# sensors_power.net
KiCad netlist of a schematic drawn in Altium Designer
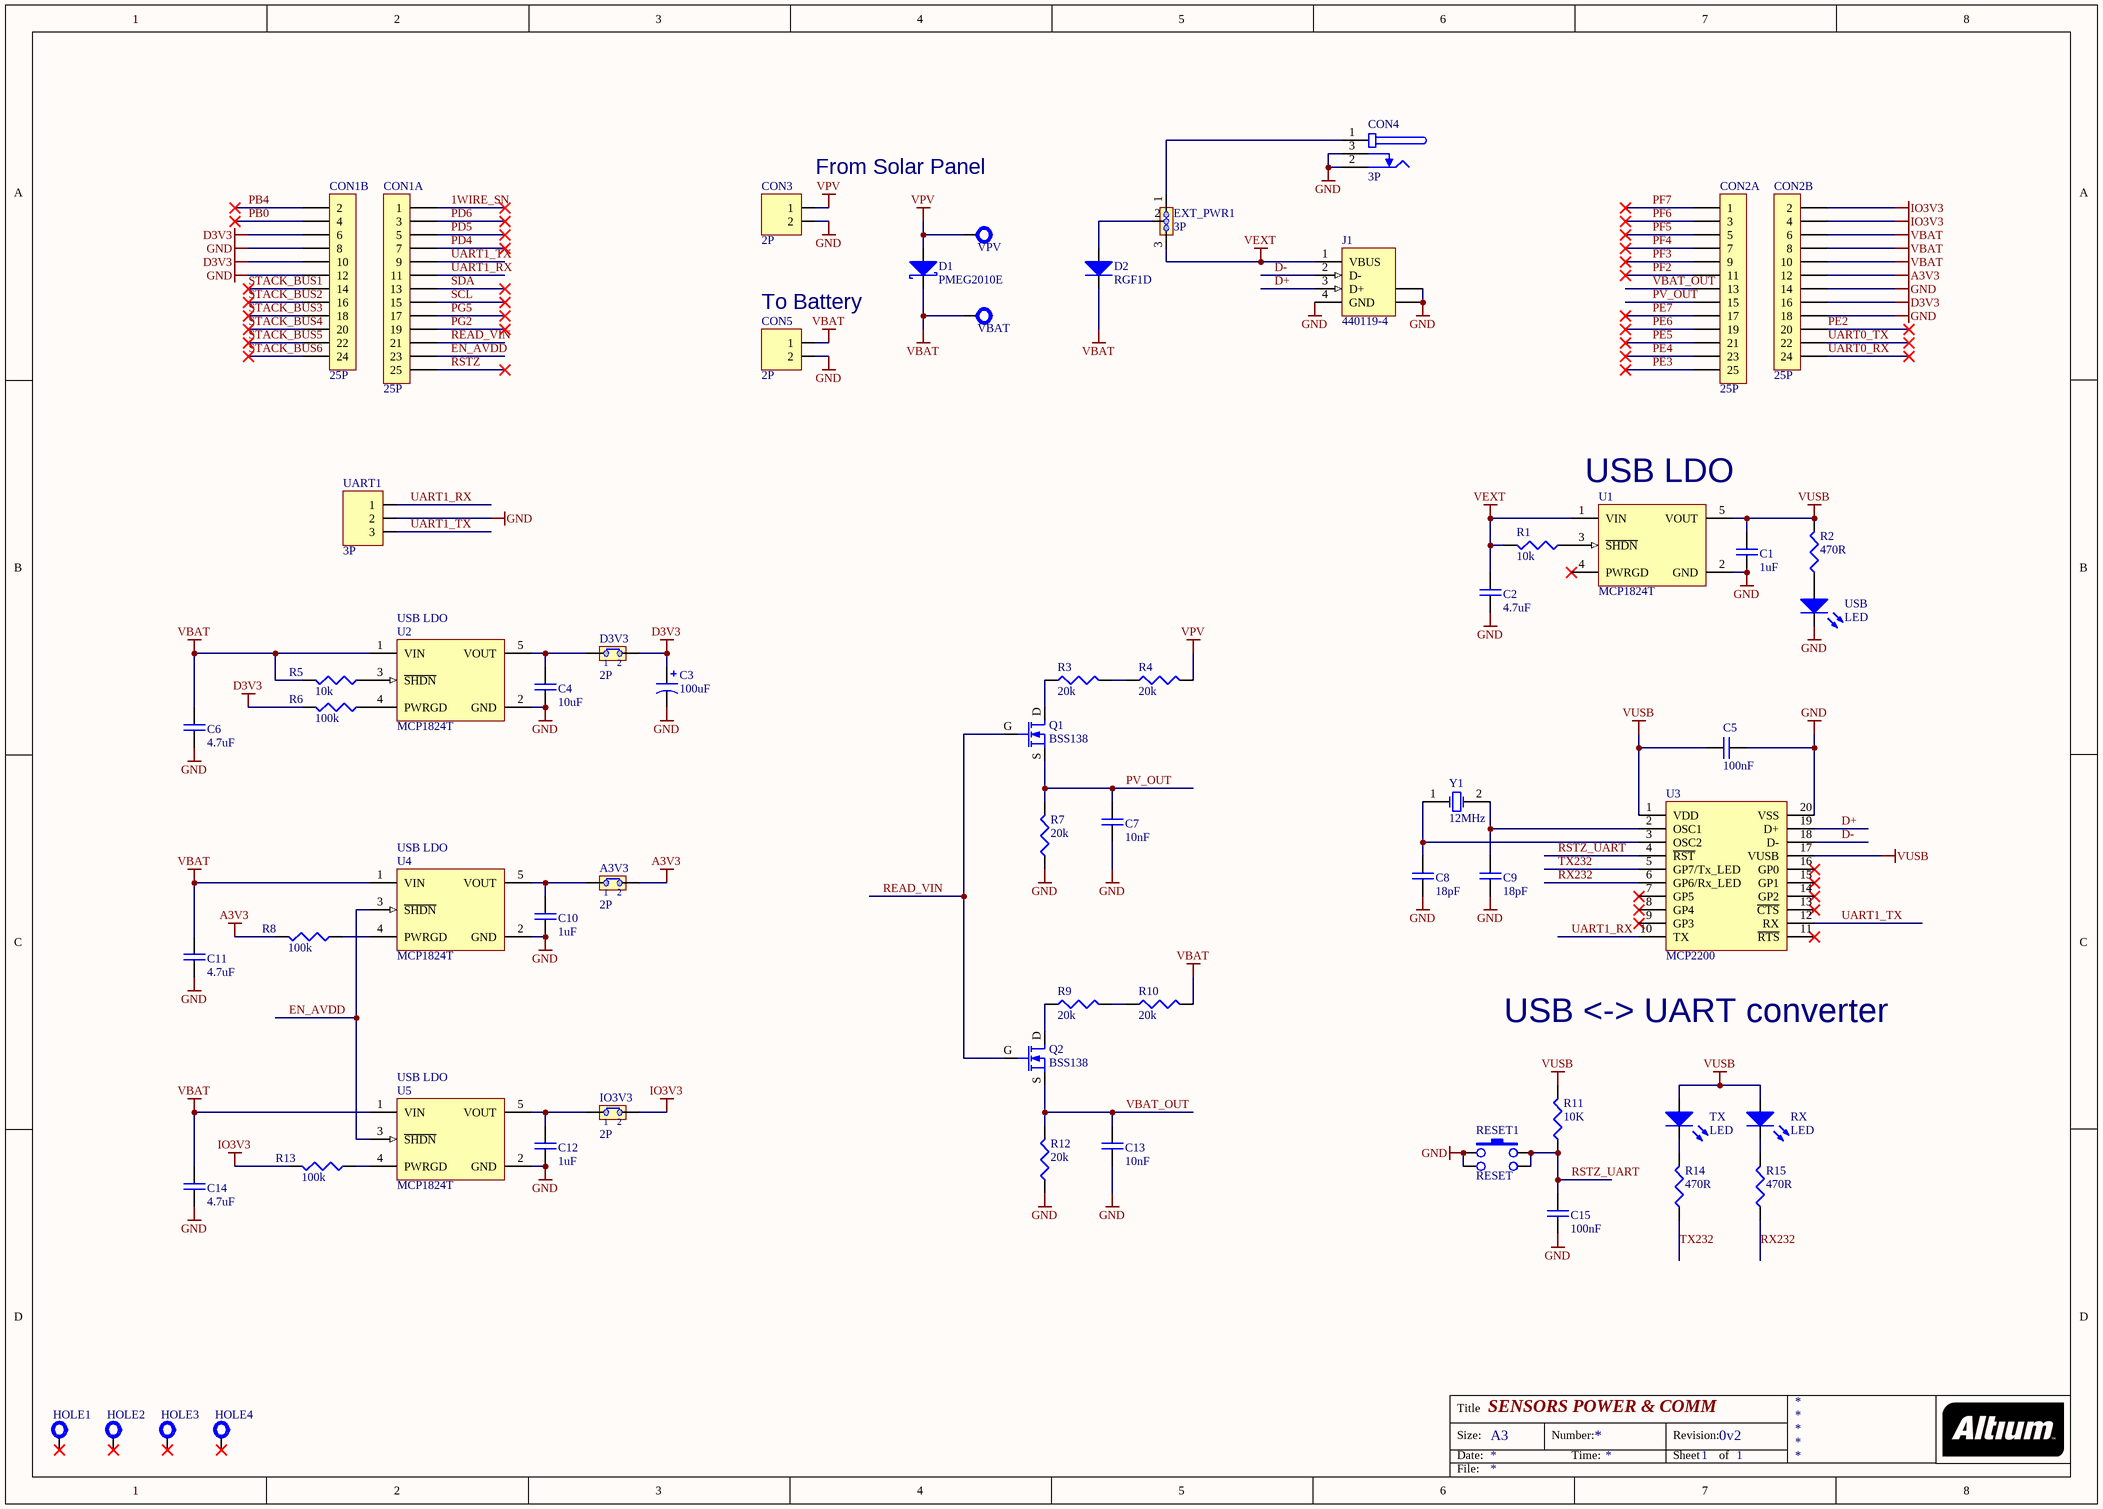
[diagram p0: sensors_power.SchDoc]

(export (version "E")
  (design (tool "Eeschema 10.0.6"))
  (components
    (comp (ref "A3V3")
      (value "2P")
      (footprint "SIP-2")
      (description "2-pin Jumper")
      (fields (field (name "OWNER") "Nuno Brum"))
      (libsource (lib "Alcetronics_EM") (part "JMP2"))
    )
    (comp (ref "C1")
      (value "1uF")
      (footprint "0805")
      (description "Capacitor")
      (fields (field (name "OWNER") "Nuno Brum"))
      (libsource (lib "Alcetronics_Devices") (part "CAP"))
    )
    (comp (ref "C2")
      (value "4.7uF")
      (footprint "0805")
      (description "Capacitor")
      (fields (field (name "OWNER") "Nuno Brum"))
      (libsource (lib "Alcetronics_Devices") (part "CAP"))
    )
    (comp (ref "C3")
      (value "100uF")
      (footprint "RADIAL-2.5MM")
      (description "Polarized Capacitor")
      (fields (field (name "OWNER") "Nuno Brum"))
      (libsource (lib "Alcetronics_Devices") (part "CAP POL"))
    )
    (comp (ref "C4")
      (value "10uF")
      (footprint "0805")
      (description "Capacitor")
      (fields (field (name "OWNER") "Nuno Brum"))
      (libsource (lib "Alcetronics_Devices") (part "CAP"))
    )
    (comp (ref "C5")
      (value "100nF")
      (footprint "0603")
      (description "Capacitor")
      (fields (field (name "OWNER") "Nuno Brum"))
      (libsource (lib "Alcetronics_Devices") (part "CAP"))
    )
    (comp (ref "C6")
      (value "4.7uF")
      (footprint "0805")
      (description "Capacitor")
      (fields (field (name "OWNER") "Nuno Brum"))
      (libsource (lib "Alcetronics_Devices") (part "CAP"))
    )
    (comp (ref "C7")
      (value "10nF")
      (footprint "0603")
      (description "Capacitor")
      (fields (field (name "OWNER") "Nuno Brum"))
      (libsource (lib "Alcetronics_Devices") (part "CAP"))
    )
    (comp (ref "C8")
      (value "18pF")
      (footprint "0603")
      (description "Capacitor")
      (fields (field (name "OWNER") "Nuno Brum"))
      (libsource (lib "Alcetronics_Devices") (part "CAP"))
    )
    (comp (ref "C9")
      (value "18pF")
      (footprint "0603")
      (description "Capacitor")
      (fields (field (name "OWNER") "Nuno Brum"))
      (libsource (lib "Alcetronics_Devices") (part "CAP"))
    )
    (comp (ref "C10")
      (value "1uF")
      (footprint "0805")
      (description "Capacitor")
      (fields (field (name "OWNER") "Nuno Brum"))
      (libsource (lib "Alcetronics_Devices") (part "CAP"))
    )
    (comp (ref "C11")
      (value "4.7uF")
      (footprint "0805")
      (description "Capacitor")
      (fields (field (name "OWNER") "Nuno Brum"))
      (libsource (lib "Alcetronics_Devices") (part "CAP"))
    )
    (comp (ref "C12")
      (value "1uF")
      (footprint "0805")
      (description "Capacitor")
      (fields (field (name "OWNER") "Nuno Brum"))
      (libsource (lib "Alcetronics_Devices") (part "CAP"))
    )
    (comp (ref "C13")
      (value "10nF")
      (footprint "0603")
      (description "Capacitor")
      (fields (field (name "OWNER") "Nuno Brum"))
      (libsource (lib "Alcetronics_Devices") (part "CAP"))
    )
    (comp (ref "C14")
      (value "4.7uF")
      (footprint "0805")
      (description "Capacitor")
      (fields (field (name "OWNER") "Nuno Brum"))
      (libsource (lib "Alcetronics_Devices") (part "CAP"))
    )
    (comp (ref "C15")
      (value "100nF")
      (footprint "0603")
      (description "Capacitor")
      (fields (field (name "OWNER") "Nuno Brum"))
      (libsource (lib "Alcetronics_Devices") (part "CAP"))
    )
    (comp (ref "CON1")
      (value "25P")
      (footprint "DF9-25")
      (description "Connector 25 Pins")
      (fields (field (name "OWNER") "Ricardo Rodrigues"))
      (libsource (lib "") (part "CON25_1"))
    )
    (comp (ref "CON2")
      (value "25P")
      (footprint "DF9-25")
      (description "Connector 25 Pins")
      (fields (field (name "OWNER") "Ricardo Rodrigues"))
      (libsource (lib "Alcetronics_EM") (part "CON25"))
    )
    (comp (ref "CON3")
      (value "2P")
      (footprint "JST-2MM")
      (description "Connector 2 pins")
      (fields (field (name "OWNER") "Rui Rebelo"))
      (libsource (lib "Alcetronics_EM") (part "CON02"))
    )
    (comp (ref "CON4")
      (value "3P")
      (footprint "JACKPOW/PD-2.5MM-TH")
      (description "Jack Power with insertion detect")
      (fields (field (name "OWNER") "Gonçalo Costa"))
      (libsource (lib "Alcetronics_EM") (part "JACK POWER PD"))
    )
    (comp (ref "CON5")
      (value "2P")
      (footprint "INTERLOCK2-5MM")
      (description "Connector 2 pins")
      (fields (field (name "OWNER") "Rui Rebelo"))
      (libsource (lib "Alcetronics_EM") (part "CON02"))
    )
    (comp (ref "D1")
      (value "PMEG2010E")
      (footprint "SOD-123")
      (description "Small Signal Schottky Diode")
      (fields (field (name "OWNER") "Nuno Brum"))
      (libsource (lib "Alcetronics_Devices") (part "Diode Schottky"))
    )
    (comp (ref "D2")
      (value "RGF1D")
      (footprint "DO-214BA")
      (description "Vishay Standard Avalanche Sinterglass Diode")
      (fields (field (name "OWNER") "Nuno Brum"))
      (libsource (lib "Alcetronics_Devices") (part "Diode"))
    )
    (comp (ref "D3V3")
      (value "2P")
      (footprint "SIP-2")
      (description "2-pin Jumper")
      (fields (field (name "OWNER") "Nuno Brum"))
      (libsource (lib "Alcetronics_EM") (part "JMP2"))
    )
    (comp (ref "EXT_PWR1")
      (value "3P")
      (footprint "SIP-3")
      (description "3-Jumper")
      (fields (field (name "OWNER") "Nuno Brum"))
      (libsource (lib "Alcetronics_EM") (part "JMP3"))
    )
    (comp (ref "HOLE1")
      (value "HOLE")
      (footprint "NPTH-3MM")
      (description "PCB Fixation Hole M3")
      (fields (field (name "OWNER") "Nuno Brum"))
      (libsource (lib "Alcetronics_EM") (part "PCB HOLE"))
    )
    (comp (ref "HOLE2")
      (value "HOLE")
      (footprint "NPTH-3MM")
      (description "PCB Fixation Hole M3")
      (fields (field (name "OWNER") "Nuno Brum"))
      (libsource (lib "Alcetronics_EM") (part "PCB HOLE"))
    )
    (comp (ref "HOLE3")
      (value "HOLE")
      (footprint "NPTH-3MM")
      (description "PCB Fixation Hole M3")
      (fields (field (name "OWNER") "Nuno Brum"))
      (libsource (lib "Alcetronics_EM") (part "PCB HOLE"))
    )
    (comp (ref "HOLE4")
      (value "HOLE")
      (footprint "NPTH-3MM")
      (description "PCB Fixation Hole M3")
      (fields (field (name "OWNER") "Nuno Brum"))
      (libsource (lib "Alcetronics_EM") (part "PCB HOLE"))
    )
    (comp (ref "IO3V3")
      (value "2P")
      (footprint "SIP-2")
      (description "2-pin Jumper")
      (fields (field (name "OWNER") "Nuno Brum"))
      (libsource (lib "Alcetronics_EM") (part "JMP2"))
    )
    (comp (ref "J1")
      (value "440119-4")
      (footprint "440119")
      (description "USB 1.1, Right Angle, Thru-Hole, B Type, Receptacle, 4 Position, Black")
      (fields (field (name "PUBLISHER") "Altium Limited"))
      (libsource (lib "Alcetronics_EM") (part "440119-4"))
    )
    (comp (ref "Q1")
      (value "BSS138")
      (footprint "SOT-23@GSD")
      (description "N-Channel Logic Level Enhancement Mode Field Effect Transistor")
      (fields (field (name "OWNER") "Nuno Brum"))
      (libsource (lib "Alcetronics_Devices") (part "MOSFET-N"))
    )
    (comp (ref "Q2")
      (value "BSS138")
      (footprint "SOT-23@GSD")
      (description "N-Channel Logic Level Enhancement Mode Field Effect Transistor")
      (fields (field (name "OWNER") "Nuno Brum"))
      (libsource (lib "Alcetronics_Devices") (part "MOSFET-N"))
    )
    (comp (ref "R1")
      (value "10k")
      (footprint "0603")
      (description "Resistor")
      (fields (field (name "OWNER") "Nuno Brum"))
      (libsource (lib "Alcetronics_Devices") (part "RES"))
    )
    (comp (ref "R2")
      (value "470R")
      (footprint "0603")
      (description "Resistor")
      (fields (field (name "OWNER") "Nuno Brum"))
      (libsource (lib "Alcetronics_Devices") (part "RES"))
    )
    (comp (ref "R3")
      (value "20k")
      (footprint "0603")
      (description "Resistor")
      (fields (field (name "OWNER") "Nuno Brum"))
      (libsource (lib "Alcetronics_Devices") (part "RES"))
    )
    (comp (ref "R4")
      (value "20k")
      (footprint "0603")
      (description "Resistor")
      (fields (field (name "OWNER") "Nuno Brum"))
      (libsource (lib "Alcetronics_Devices") (part "RES"))
    )
    (comp (ref "R5")
      (value "10k")
      (footprint "0603")
      (description "Resistor")
      (fields (field (name "OWNER") "Nuno Brum"))
      (libsource (lib "Alcetronics_Devices") (part "RES"))
    )
    (comp (ref "R6")
      (value "100k")
      (footprint "0603")
      (description "Resistor")
      (fields (field (name "OWNER") "Nuno Brum"))
      (libsource (lib "Alcetronics_Devices") (part "RES"))
    )
    (comp (ref "R7")
      (value "20k")
      (footprint "0603")
      (description "Resistor")
      (fields (field (name "OWNER") "Nuno Brum"))
      (libsource (lib "Alcetronics_Devices") (part "RES"))
    )
    (comp (ref "R8")
      (value "100k")
      (footprint "0603")
      (description "Resistor")
      (fields (field (name "OWNER") "Nuno Brum"))
      (libsource (lib "Alcetronics_Devices") (part "RES"))
    )
    (comp (ref "R9")
      (value "20k")
      (footprint "0603")
      (description "Resistor")
      (fields (field (name "OWNER") "Nuno Brum"))
      (libsource (lib "Alcetronics_Devices") (part "RES"))
    )
    (comp (ref "R10")
      (value "20k")
      (footprint "0603")
      (description "Resistor")
      (fields (field (name "OWNER") "Nuno Brum"))
      (libsource (lib "Alcetronics_Devices") (part "RES"))
    )
    (comp (ref "R11")
      (value "10K")
      (footprint "0603")
      (description "Resistor")
      (fields (field (name "OWNER") "Nuno Brum"))
      (libsource (lib "Alcetronics_Devices") (part "RES"))
    )
    (comp (ref "R12")
      (value "20k")
      (footprint "0603")
      (description "Resistor")
      (fields (field (name "OWNER") "Nuno Brum"))
      (libsource (lib "Alcetronics_Devices") (part "RES"))
    )
    (comp (ref "R13")
      (value "100k")
      (footprint "0603")
      (description "Resistor")
      (fields (field (name "OWNER") "Nuno Brum"))
      (libsource (lib "Alcetronics_Devices") (part "RES"))
    )
    (comp (ref "R14")
      (value "470R")
      (footprint "0603")
      (description "Resistor")
      (fields (field (name "OWNER") "Nuno Brum"))
      (libsource (lib "Alcetronics_Devices") (part "RES"))
    )
    (comp (ref "R15")
      (value "470R")
      (footprint "0603")
      (description "Resistor")
      (fields (field (name "OWNER") "Nuno Brum"))
      (libsource (lib "Alcetronics_Devices") (part "RES"))
    )
    (comp (ref "RESET1")
      (value "RESET")
      (footprint "MICROSWITCH")
      (description "Switch Push Button")
      (fields (field (name "OWNER") "Nuno Brum"))
      (libsource (lib "Alcetronics_EM") (part "SW1"))
    )
    (comp (ref "RX")
      (value "LED")
      (footprint "0805@DIODE")
      (description "Light emitting diode")
      (fields (field (name "OWNER") "Nuno Brum"))
      (libsource (lib "Alcetronics_Devices") (part "LED"))
    )
    (comp (ref "TX")
      (value "LED")
      (footprint "0805@DIODE")
      (description "Light emitting diode")
      (fields (field (name "OWNER") "Nuno Brum"))
      (libsource (lib "Alcetronics_Devices") (part "LED"))
    )
    (comp (ref "U1")
      (value "MCP1824T")
      (footprint "SOT-23-5")
      (fields (field (name "PUBLISHER") "Altium Limited"))
      (libsource (lib "Alcetronics_IC") (part "MCP1824T"))
    )
    (comp (ref "U2")
      (value "MCP1824T")
      (footprint "SOT-23-5")
      (fields (field (name "PUBLISHER") "Altium Limited"))
      (libsource (lib "Alcetronics_IC") (part "MCP1824T"))
    )
    (comp (ref "U3")
      (value "MCP2200")
      (footprint "SOIC-20")
      (description "USB to Serial interface")
      (fields (field (name "PUBLISHER") "Altium Limited"))
      (libsource (lib "Alcetronics_IC") (part "MCP2200"))
    )
    (comp (ref "U4")
      (value "MCP1824T")
      (footprint "SOT-23-5")
      (fields (field (name "PUBLISHER") "Altium Limited"))
      (libsource (lib "Alcetronics_IC") (part "MCP1824T"))
    )
    (comp (ref "U5")
      (value "MCP1824T")
      (footprint "SOT-23-5")
      (fields (field (name "PUBLISHER") "Altium Limited"))
      (libsource (lib "Alcetronics_IC") (part "MCP1824T"))
    )
    (comp (ref "UART1")
      (value "3P")
      (footprint "SIP-3")
      (description "Connector 3 pins")
      (fields (field (name "OWNER") "Rui Rebelo"))
      (libsource (lib "Alcetronics_EM") (part "CON03"))
    )
    (comp (ref "USB")
      (value "LED")
      (footprint "0805@DIODE")
      (description "Light emitting diode")
      (fields (field (name "OWNER") "Nuno Brum"))
      (libsource (lib "Alcetronics_Devices") (part "LED"))
    )
    (comp (ref "VBAT")
      (value "Test Point")
      (footprint "TERMINAL")
      (description "Test/Probe Point")
      (fields (field (name "OWNER") "Nuno Brum"))
      (libsource (lib "Alcetronics_EM") (part "TEST-PROBE"))
    )
    (comp (ref "VPV")
      (value "Test Point")
      (footprint "TERMINAL")
      (description "Test/Probe Point")
      (fields (field (name "OWNER") "Nuno Brum"))
      (libsource (lib "Alcetronics_EM") (part "TEST-PROBE"))
    )
    (comp (ref "Y1")
      (value "12MHz")
      (footprint "CSM-7")
      (description "Crystal Oscillator")
      (fields (field (name "PUBLISHER") "Altium Limited"))
      (libsource (lib "Alcetronics_Devices") (part "Crystal Oscillator"))
    )
  )
  (nets
    (net (code "1") (name "/1WIRE_SN") (class "Default")
      (node (ref "CON1") (pin "1") (pinfunction "1_1") (pintype "passive+no_connect"))
    )
    (net (code "2") (name "/D+") (class "Default")
      (node (ref "J1") (pin "3") (pinfunction "D+_3") (pintype "input"))
      (node (ref "U3") (pin "19") (pinfunction "D+_19") (pintype "passive"))
    )
    (net (code "3") (name "/D-") (class "Default")
      (node (ref "J1") (pin "2") (pinfunction "D-_2") (pintype "input"))
      (node (ref "U3") (pin "18") (pinfunction "D-_18") (pintype "passive"))
    )
    (net (code "4") (name "/EN_AVDD") (class "Default")
      (node (ref "CON1") (pin "23") (pinfunction "23_23") (pintype "passive"))
      (node (ref "U4") (pin "3") (pinfunction "~{SHDN}_3") (pintype "input"))
      (node (ref "U5") (pin "3") (pinfunction "~{SHDN}_3") (pintype "input"))
    )
    (net (code "5") (name "/PB0") (class "Default")
      (node (ref "CON1") (pin "4") (pinfunction "4_4") (pintype "passive+no_connect"))
    )
    (net (code "6") (name "/PB4") (class "Default")
      (node (ref "CON1") (pin "2") (pinfunction "2_2") (pintype "passive+no_connect"))
    )
    (net (code "7") (name "/PD4") (class "Default")
      (node (ref "CON1") (pin "7") (pinfunction "7_7") (pintype "passive+no_connect"))
    )
    (net (code "8") (name "/PD5") (class "Default")
      (node (ref "CON1") (pin "5") (pinfunction "5_5") (pintype "passive+no_connect"))
    )
    (net (code "9") (name "/PD6") (class "Default")
      (node (ref "CON1") (pin "3") (pinfunction "3_3") (pintype "passive+no_connect"))
    )
    (net (code "10") (name "/PE2") (class "Default")
      (node (ref "CON2") (pin "20") (pinfunction "20_20") (pintype "passive+no_connect"))
    )
    (net (code "11") (name "/PE3") (class "Default")
      (node (ref "CON2") (pin "25") (pinfunction "25_25") (pintype "passive+no_connect"))
    )
    (net (code "12") (name "/PE4") (class "Default")
      (node (ref "CON2") (pin "23") (pinfunction "23_23") (pintype "passive+no_connect"))
    )
    (net (code "13") (name "/PE5") (class "Default")
      (node (ref "CON2") (pin "21") (pinfunction "21_21") (pintype "passive+no_connect"))
    )
    (net (code "14") (name "/PE6") (class "Default")
      (node (ref "CON2") (pin "19") (pinfunction "19_19") (pintype "passive+no_connect"))
    )
    (net (code "15") (name "/PE7") (class "Default")
      (node (ref "CON2") (pin "17") (pinfunction "17_17") (pintype "passive+no_connect"))
    )
    (net (code "16") (name "/PF2") (class "Default")
      (node (ref "CON2") (pin "11") (pinfunction "11_11") (pintype "passive+no_connect"))
    )
    (net (code "17") (name "/PF3") (class "Default")
      (node (ref "CON2") (pin "9") (pinfunction "9_9") (pintype "passive+no_connect"))
    )
    (net (code "18") (name "/PF4") (class "Default")
      (node (ref "CON2") (pin "7") (pinfunction "7_7") (pintype "passive+no_connect"))
    )
    (net (code "19") (name "/PF5") (class "Default")
      (node (ref "CON2") (pin "5") (pinfunction "5_5") (pintype "passive+no_connect"))
    )
    (net (code "20") (name "/PF6") (class "Default")
      (node (ref "CON2") (pin "3") (pinfunction "3_3") (pintype "passive+no_connect"))
    )
    (net (code "21") (name "/PF7") (class "Default")
      (node (ref "CON2") (pin "1") (pinfunction "1_1") (pintype "passive+no_connect"))
    )
    (net (code "22") (name "/PG2") (class "Default")
      (node (ref "CON1") (pin "19") (pinfunction "19_19") (pintype "passive+no_connect"))
    )
    (net (code "23") (name "/PG5") (class "Default")
      (node (ref "CON1") (pin "17") (pinfunction "17_17") (pintype "passive+no_connect"))
    )
    (net (code "24") (name "/PV_OUT") (class "Default")
      (node (ref "C7") (pin "2") (pinfunction "2_2") (pintype "passive"))
      (node (ref "CON2") (pin "15") (pinfunction "15_15") (pintype "passive"))
      (node (ref "Q1") (pin "S") (pinfunction "S_S") (pintype "passive"))
      (node (ref "R7") (pin "2") (pinfunction "2_2") (pintype "passive"))
    )
    (net (code "25") (name "/READ_VIN") (class "Default")
      (node (ref "CON1") (pin "21") (pinfunction "21_21") (pintype "passive"))
      (node (ref "Q1") (pin "G") (pinfunction "G_G") (pintype "passive"))
      (node (ref "Q2") (pin "G") (pinfunction "G_G") (pintype "passive"))
    )
    (net (code "26") (name "/RSTZ") (class "Default")
      (node (ref "CON1") (pin "25") (pinfunction "25_25") (pintype "passive+no_connect"))
    )
    (net (code "27") (name "/RSTZ_UART") (class "Default")
      (node (ref "C15") (pin "2") (pinfunction "2_2") (pintype "passive"))
      (node (ref "R11") (pin "1") (pinfunction "1_1") (pintype "passive"))
      (node (ref "RESET1") (pin "2") (pinfunction "2_2") (pintype "passive"))
      (node (ref "RESET1") (pin "4") (pinfunction "4_4") (pintype "passive"))
      (node (ref "U3") (pin "4") (pinfunction "~{RST}_4") (pintype "passive"))
    )
    (net (code "28") (name "/RX232") (class "Default")
      (node (ref "R15") (pin "1") (pinfunction "1_1") (pintype "passive"))
      (node (ref "U3") (pin "6") (pinfunction "GP6/Rx_LED_6") (pintype "passive"))
    )
    (net (code "29") (name "/SCL") (class "Default")
      (node (ref "CON1") (pin "15") (pinfunction "15_15") (pintype "passive+no_connect"))
    )
    (net (code "30") (name "/SDA") (class "Default")
      (node (ref "CON1") (pin "13") (pinfunction "13_13") (pintype "passive+no_connect"))
    )
    (net (code "31") (name "/STACK_BUS1") (class "Default")
      (node (ref "CON1") (pin "14") (pinfunction "14_14") (pintype "passive+no_connect"))
    )
    (net (code "32") (name "/STACK_BUS2") (class "Default")
      (node (ref "CON1") (pin "16") (pinfunction "16_16") (pintype "passive+no_connect"))
    )
    (net (code "33") (name "/STACK_BUS3") (class "Default")
      (node (ref "CON1") (pin "18") (pinfunction "18_18") (pintype "passive+no_connect"))
    )
    (net (code "34") (name "/STACK_BUS4") (class "Default")
      (node (ref "CON1") (pin "20") (pinfunction "20_20") (pintype "passive+no_connect"))
    )
    (net (code "35") (name "/STACK_BUS5") (class "Default")
      (node (ref "CON1") (pin "22") (pinfunction "22_22") (pintype "passive+no_connect"))
    )
    (net (code "36") (name "/STACK_BUS6") (class "Default")
      (node (ref "CON1") (pin "24") (pinfunction "24_24") (pintype "passive+no_connect"))
    )
    (net (code "37") (name "/TX232") (class "Default")
      (node (ref "R14") (pin "1") (pinfunction "1_1") (pintype "passive"))
      (node (ref "U3") (pin "5") (pinfunction "GP7/Tx_LED_5") (pintype "passive"))
    )
    (net (code "38") (name "/UART0_RX") (class "Default")
      (node (ref "CON2") (pin "24") (pinfunction "24_24") (pintype "passive+no_connect"))
    )
    (net (code "39") (name "/UART0_TX") (class "Default")
      (node (ref "CON2") (pin "22") (pinfunction "22_22") (pintype "passive+no_connect"))
    )
    (net (code "40") (name "/UART1_RX") (class "Default")
      (node (ref "CON1") (pin "11") (pinfunction "11_11") (pintype "passive"))
      (node (ref "U3") (pin "10") (pinfunction "TX_10") (pintype "passive"))
      (node (ref "UART1") (pin "1") (pinfunction "1_1") (pintype "passive"))
    )
    (net (code "41") (name "/UART1_TX") (class "Default")
      (node (ref "CON1") (pin "9") (pinfunction "9_9") (pintype "passive"))
      (node (ref "U3") (pin "12") (pinfunction "RX_12") (pintype "passive"))
      (node (ref "UART1") (pin "3") (pinfunction "3_3") (pintype "passive"))
    )
    (net (code "42") (name "/VBAT_OUT") (class "Default")
      (node (ref "C13") (pin "2") (pinfunction "2_2") (pintype "passive"))
      (node (ref "CON2") (pin "13") (pinfunction "13_13") (pintype "passive"))
      (node (ref "Q2") (pin "S") (pinfunction "S_S") (pintype "passive"))
      (node (ref "R12") (pin "2") (pinfunction "2_2") (pintype "passive"))
    )
    (net (code "43") (name "A3V3") (class "Default")
      (node (ref "A3V3") (pin "2") (pinfunction "2_2") (pintype "passive"))
      (node (ref "CON2") (pin "12") (pinfunction "12_12") (pintype "passive"))
      (node (ref "R8") (pin "2") (pinfunction "2_2") (pintype "passive"))
    )
    (net (code "44") (name "D3V3") (class "Default")
      (node (ref "C3") (pin "1") (pinfunction "P_1") (pintype "passive"))
      (node (ref "CON1") (pin "10") (pinfunction "10_10") (pintype "passive"))
      (node (ref "CON1") (pin "6") (pinfunction "6_6") (pintype "passive"))
      (node (ref "CON2") (pin "16") (pinfunction "16_16") (pintype "passive"))
      (node (ref "D3V3") (pin "2") (pinfunction "2_2") (pintype "passive"))
      (node (ref "R6") (pin "2") (pinfunction "2_2") (pintype "passive"))
    )
    (net (code "45") (name "GND") (class "Default")
      (node (ref "C1") (pin "1") (pinfunction "1_1") (pintype "passive"))
      (node (ref "C10") (pin "1") (pinfunction "1_1") (pintype "passive"))
      (node (ref "C11") (pin "1") (pinfunction "1_1") (pintype "passive"))
      (node (ref "C12") (pin "1") (pinfunction "1_1") (pintype "passive"))
      (node (ref "C13") (pin "1") (pinfunction "1_1") (pintype "passive"))
      (node (ref "C14") (pin "1") (pinfunction "1_1") (pintype "passive"))
      (node (ref "C15") (pin "1") (pinfunction "1_1") (pintype "passive"))
      (node (ref "C2") (pin "1") (pinfunction "1_1") (pintype "passive"))
      (node (ref "C3") (pin "2") (pinfunction "N_2") (pintype "passive"))
      (node (ref "C4") (pin "1") (pinfunction "1_1") (pintype "passive"))
      (node (ref "C5") (pin "1") (pinfunction "1_1") (pintype "passive"))
      (node (ref "C6") (pin "1") (pinfunction "1_1") (pintype "passive"))
      (node (ref "C7") (pin "1") (pinfunction "1_1") (pintype "passive"))
      (node (ref "C8") (pin "1") (pinfunction "1_1") (pintype "passive"))
      (node (ref "C9") (pin "1") (pinfunction "1_1") (pintype "passive"))
      (node (ref "CON1") (pin "12") (pinfunction "12_12") (pintype "passive"))
      (node (ref "CON1") (pin "8") (pinfunction "8_8") (pintype "passive"))
      (node (ref "CON2") (pin "14") (pinfunction "14_14") (pintype "passive"))
      (node (ref "CON2") (pin "18") (pinfunction "18_18") (pintype "passive"))
      (node (ref "CON3") (pin "2") (pinfunction "2_2") (pintype "passive"))
      (node (ref "CON4") (pin "2") (pinfunction "2_2") (pintype "passive"))
      (node (ref "CON4") (pin "3") (pinfunction "3_3") (pintype "passive"))
      (node (ref "CON5") (pin "2") (pinfunction "2_2") (pintype "passive"))
      (node (ref "J1") (pin "4") (pinfunction "GND_4") (pintype "power_in"))
      (node (ref "J1") (pin "5") (pinfunction "SHLD_5") (pintype "passive"))
      (node (ref "J1") (pin "6") (pinfunction "SHLD_6") (pintype "passive"))
      (node (ref "R12") (pin "1") (pinfunction "1_1") (pintype "passive"))
      (node (ref "R7") (pin "1") (pinfunction "1_1") (pintype "passive"))
      (node (ref "RESET1") (pin "1") (pinfunction "1_1") (pintype "passive"))
      (node (ref "RESET1") (pin "3") (pinfunction "3_3") (pintype "passive"))
      (node (ref "U1") (pin "2") (pinfunction "GND_2") (pintype "power_in"))
      (node (ref "U2") (pin "2") (pinfunction "GND_2") (pintype "power_in"))
      (node (ref "U3") (pin "20") (pinfunction "VSS_20") (pintype "power_in"))
      (node (ref "U4") (pin "2") (pinfunction "GND_2") (pintype "power_in"))
      (node (ref "U5") (pin "2") (pinfunction "GND_2") (pintype "power_in"))
      (node (ref "UART1") (pin "2") (pinfunction "2_2") (pintype "passive"))
      (node (ref "USB") (pin "K") (pinfunction "K_K") (pintype "passive"))
    )
    (net (code "46") (name "IO3V3") (class "Default")
      (node (ref "CON2") (pin "2") (pinfunction "2_2") (pintype "passive"))
      (node (ref "CON2") (pin "4") (pinfunction "4_4") (pintype "passive"))
      (node (ref "IO3V3") (pin "2") (pinfunction "2_2") (pintype "passive"))
      (node (ref "R13") (pin "2") (pinfunction "2_2") (pintype "passive"))
    )
    (net (code "47") (name "Net-(CON4-Pad1)") (class "Default")
      (node (ref "CON4") (pin "1") (pinfunction "1_1") (pintype "passive"))
      (node (ref "EXT_PWR1") (pin "1") (pinfunction "1_1") (pintype "passive"))
    )
    (net (code "48") (name "Net-(D2-PadA)") (class "Default")
      (node (ref "D2") (pin "A") (pinfunction "A_A") (pintype "passive"))
      (node (ref "EXT_PWR1") (pin "2") (pinfunction "2_2") (pintype "passive"))
    )
    (net (code "49") (name "Net-(Q1-PadD)") (class "Default")
      (node (ref "Q1") (pin "D") (pinfunction "D_D") (pintype "passive"))
      (node (ref "R3") (pin "1") (pinfunction "1_1") (pintype "passive"))
    )
    (net (code "50") (name "Net-(Q2-PadD)") (class "Default")
      (node (ref "Q2") (pin "D") (pinfunction "D_D") (pintype "passive"))
      (node (ref "R9") (pin "1") (pinfunction "1_1") (pintype "passive"))
    )
    (net (code "51") (name "Net-(R2-Pad1)") (class "Default")
      (node (ref "R2") (pin "1") (pinfunction "1_1") (pintype "passive"))
      (node (ref "USB") (pin "A") (pinfunction "A_A") (pintype "passive"))
    )
    (net (code "52") (name "Net-(R3-Pad2)") (class "Default")
      (node (ref "R3") (pin "2") (pinfunction "2_2") (pintype "passive"))
      (node (ref "R4") (pin "1") (pinfunction "1_1") (pintype "passive"))
    )
    (net (code "53") (name "Net-(R10-Pad1)") (class "Default")
      (node (ref "R10") (pin "1") (pinfunction "1_1") (pintype "passive"))
      (node (ref "R9") (pin "2") (pinfunction "2_2") (pintype "passive"))
    )
    (net (code "54") (name "Net-(R14-Pad2)") (class "Default")
      (node (ref "R14") (pin "2") (pinfunction "2_2") (pintype "passive"))
      (node (ref "TX") (pin "K") (pinfunction "K_K") (pintype "passive"))
    )
    (net (code "55") (name "Net-(R15-Pad2)") (class "Default")
      (node (ref "R15") (pin "2") (pinfunction "2_2") (pintype "passive"))
      (node (ref "RX") (pin "K") (pinfunction "K_K") (pintype "passive"))
    )
    (net (code "56") (name "Net-(U1-~{SHDN})") (class "Default")
      (node (ref "R1") (pin "1") (pinfunction "1_1") (pintype "passive"))
      (node (ref "U1") (pin "3") (pinfunction "~{SHDN}_3") (pintype "input"))
    )
    (net (code "57") (name "Net-(U2-PWRGD)") (class "Default")
      (node (ref "R6") (pin "1") (pinfunction "1_1") (pintype "passive"))
      (node (ref "U2") (pin "4") (pinfunction "PWRGD_4") (pintype "power_in"))
    )
    (net (code "58") (name "Net-(U2-VOUT)") (class "Default")
      (node (ref "C4") (pin "2") (pinfunction "2_2") (pintype "passive"))
      (node (ref "D3V3") (pin "1") (pinfunction "1_1") (pintype "passive"))
      (node (ref "U2") (pin "5") (pinfunction "VOUT_5") (pintype "power_in"))
    )
    (net (code "59") (name "Net-(U2-~{SHDN})") (class "Default")
      (node (ref "R5") (pin "1") (pinfunction "1_1") (pintype "passive"))
      (node (ref "U2") (pin "3") (pinfunction "~{SHDN}_3") (pintype "input"))
    )
    (net (code "60") (name "Net-(U3-OSC1)") (class "Default")
      (node (ref "C9") (pin "2") (pinfunction "2_2") (pintype "passive"))
      (node (ref "U3") (pin "2") (pinfunction "OSC1_2") (pintype "passive"))
      (node (ref "Y1") (pin "2") (pinfunction "OSC2_2") (pintype "passive"))
    )
    (net (code "61") (name "Net-(U3-OSC2)") (class "Default")
      (node (ref "C8") (pin "2") (pinfunction "2_2") (pintype "passive"))
      (node (ref "U3") (pin "3") (pinfunction "OSC2_3") (pintype "passive"))
      (node (ref "Y1") (pin "1") (pinfunction "OSC1_1") (pintype "passive"))
    )
    (net (code "62") (name "Net-(U4-PWRGD)") (class "Default")
      (node (ref "R8") (pin "1") (pinfunction "1_1") (pintype "passive"))
      (node (ref "U4") (pin "4") (pinfunction "PWRGD_4") (pintype "power_in"))
    )
    (net (code "63") (name "Net-(U4-VOUT)") (class "Default")
      (node (ref "A3V3") (pin "1") (pinfunction "1_1") (pintype "passive"))
      (node (ref "C10") (pin "2") (pinfunction "2_2") (pintype "passive"))
      (node (ref "U4") (pin "5") (pinfunction "VOUT_5") (pintype "power_in"))
    )
    (net (code "64") (name "Net-(U5-PWRGD)") (class "Default")
      (node (ref "R13") (pin "1") (pinfunction "1_1") (pintype "passive"))
      (node (ref "U5") (pin "4") (pinfunction "PWRGD_4") (pintype "power_in"))
    )
    (net (code "65") (name "Net-(U5-VOUT)") (class "Default")
      (node (ref "C12") (pin "2") (pinfunction "2_2") (pintype "passive"))
      (node (ref "IO3V3") (pin "1") (pinfunction "1_1") (pintype "passive"))
      (node (ref "U5") (pin "5") (pinfunction "VOUT_5") (pintype "power_in"))
    )
    (net (code "66") (name "VBAT") (class "Default")
      (node (ref "C11") (pin "2") (pinfunction "2_2") (pintype "passive"))
      (node (ref "C14") (pin "2") (pinfunction "2_2") (pintype "passive"))
      (node (ref "C6") (pin "2") (pinfunction "2_2") (pintype "passive"))
      (node (ref "CON2") (pin "10") (pinfunction "10_10") (pintype "passive"))
      (node (ref "CON2") (pin "6") (pinfunction "6_6") (pintype "passive"))
      (node (ref "CON2") (pin "8") (pinfunction "8_8") (pintype "passive"))
      (node (ref "CON5") (pin "1") (pinfunction "1_1") (pintype "passive"))
      (node (ref "D1") (pin "K") (pinfunction "K_K") (pintype "passive"))
      (node (ref "D2") (pin "K") (pinfunction "K_K") (pintype "passive"))
      (node (ref "R10") (pin "2") (pinfunction "2_2") (pintype "passive"))
      (node (ref "R5") (pin "2") (pinfunction "2_2") (pintype "passive"))
      (node (ref "U2") (pin "1") (pinfunction "VIN_1") (pintype "power_in"))
      (node (ref "U4") (pin "1") (pinfunction "VIN_1") (pintype "power_in"))
      (node (ref "U5") (pin "1") (pinfunction "VIN_1") (pintype "power_in"))
      (node (ref "VBAT") (pin "1") (pinfunction "TP_1") (pintype "passive"))
    )
    (net (code "67") (name "VEXT") (class "Default")
      (node (ref "C2") (pin "2") (pinfunction "2_2") (pintype "passive"))
      (node (ref "EXT_PWR1") (pin "3") (pinfunction "3_3") (pintype "passive"))
      (node (ref "J1") (pin "1") (pinfunction "VBUS_1") (pintype "power_in"))
      (node (ref "R1") (pin "2") (pinfunction "2_2") (pintype "passive"))
      (node (ref "U1") (pin "1") (pinfunction "VIN_1") (pintype "power_in"))
    )
    (net (code "68") (name "VPV") (class "Default")
      (node (ref "CON3") (pin "1") (pinfunction "1_1") (pintype "passive"))
      (node (ref "D1") (pin "A") (pinfunction "A_A") (pintype "passive"))
      (node (ref "R4") (pin "2") (pinfunction "2_2") (pintype "passive"))
      (node (ref "VPV") (pin "1") (pinfunction "TP_1") (pintype "passive"))
    )
    (net (code "69") (name "VUSB") (class "Default")
      (node (ref "C1") (pin "2") (pinfunction "2_2") (pintype "passive"))
      (node (ref "C5") (pin "2") (pinfunction "2_2") (pintype "passive"))
      (node (ref "R11") (pin "2") (pinfunction "2_2") (pintype "passive"))
      (node (ref "R2") (pin "2") (pinfunction "2_2") (pintype "passive"))
      (node (ref "RX") (pin "A") (pinfunction "A_A") (pintype "passive"))
      (node (ref "TX") (pin "A") (pinfunction "A_A") (pintype "passive"))
      (node (ref "U1") (pin "5") (pinfunction "VOUT_5") (pintype "power_in"))
      (node (ref "U3") (pin "1") (pinfunction "VDD_1") (pintype "power_in"))
      (node (ref "U3") (pin "17") (pinfunction "VUSB_17") (pintype "power_in"))
    )
    (net (code "70") (name "unconnected-(HOLE1-TP-Pad1)") (class "Default")
      (node (ref "HOLE1") (pin "1") (pinfunction "TP_1") (pintype "passive+no_connect"))
    )
    (net (code "71") (name "unconnected-(HOLE2-TP-Pad1)") (class "Default")
      (node (ref "HOLE2") (pin "1") (pinfunction "TP_1") (pintype "passive+no_connect"))
    )
    (net (code "72") (name "unconnected-(HOLE3-TP-Pad1)") (class "Default")
      (node (ref "HOLE3") (pin "1") (pinfunction "TP_1") (pintype "passive+no_connect"))
    )
    (net (code "73") (name "unconnected-(HOLE4-TP-Pad1)") (class "Default")
      (node (ref "HOLE4") (pin "1") (pinfunction "TP_1") (pintype "passive+no_connect"))
    )
    (net (code "74") (name "unconnected-(U1-PWRGD-Pad4)") (class "Default")
      (node (ref "U1") (pin "4") (pinfunction "PWRGD_4") (pintype "power_in+no_connect"))
    )
    (net (code "75") (name "unconnected-(U3-GP0-Pad16)") (class "Default")
      (node (ref "U3") (pin "16") (pinfunction "GP0_16") (pintype "passive+no_connect"))
    )
    (net (code "76") (name "unconnected-(U3-GP1-Pad15)") (class "Default")
      (node (ref "U3") (pin "15") (pinfunction "GP1_15") (pintype "passive+no_connect"))
    )
    (net (code "77") (name "unconnected-(U3-GP2-Pad14)") (class "Default")
      (node (ref "U3") (pin "14") (pinfunction "GP2_14") (pintype "passive+no_connect"))
    )
    (net (code "78") (name "unconnected-(U3-GP3-Pad9)") (class "Default")
      (node (ref "U3") (pin "9") (pinfunction "GP3_9") (pintype "passive+no_connect"))
    )
    (net (code "79") (name "unconnected-(U3-GP4-Pad8)") (class "Default")
      (node (ref "U3") (pin "8") (pinfunction "GP4_8") (pintype "passive+no_connect"))
    )
    (net (code "80") (name "unconnected-(U3-GP5-Pad7)") (class "Default")
      (node (ref "U3") (pin "7") (pinfunction "GP5_7") (pintype "passive+no_connect"))
    )
    (net (code "81") (name "unconnected-(U3-~{CTS}-Pad13)") (class "Default")
      (node (ref "U3") (pin "13") (pinfunction "~{CTS}_13") (pintype "passive+no_connect"))
    )
    (net (code "82") (name "unconnected-(U3-~{RTS}-Pad11)") (class "Default")
      (node (ref "U3") (pin "11") (pinfunction "~{RTS}_11") (pintype "passive+no_connect"))
    )
  )
)
